# NE555DWTZD.net
KiCad netlist of a schematic drawn in Altium Designer
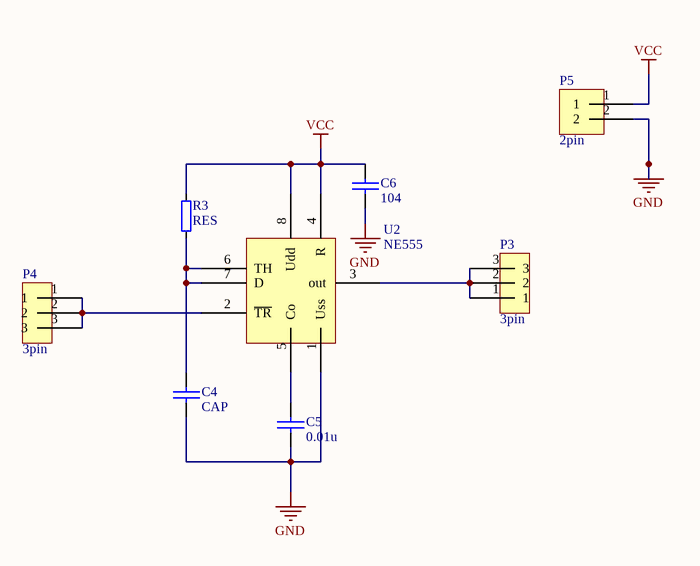
[diagram p0: NE555DWTZD.SchDoc]

(export (version "E")
  (design (tool "Eeschema 10.0.6"))
  (components
    (comp (ref "C4") (value "CAP") (footprint "RAD0.1") (libsource (lib "fish") (part "CAP")))
    (comp (ref "C5") (value "0.01u") (footprint "RAD0.1") (libsource (lib "fish") (part "CAP")))
    (comp (ref "C6") (value "104") (footprint "RAD0.1") (libsource (lib "fish") (part "CAP")))
    (comp (ref "P3") (value "3pin") (footprint "3PIN排针") (libsource (lib "") (part "3pin_1")))
    (comp (ref "P4") (value "3pin") (footprint "3PIN排针") (libsource (lib "fish") (part "3pin")))
    (comp (ref "P5") (value "2pin") (footprint "2pin针") (libsource (lib "fish") (part "2pin")))
    (comp (ref "R3") (value "RES") (footprint "AXIAL0.4") (libsource (lib "fish") (part "RES")))
    (comp (ref "U2") (value "NE555") (footprint "8pin座") (libsource (lib "fish") (part "NE555")))
  )
  (nets
    (net (code "1") (name "GND") (class "Default")
      (node (ref "C4") (pin "2") (pinfunction "2_2") (pintype "passive"))
      (node (ref "C5") (pin "2") (pinfunction "2_2") (pintype "passive"))
      (node (ref "C6") (pin "2") (pinfunction "2_2") (pintype "passive"))
      (node (ref "P5") (pin "2") (pinfunction "2_2") (pintype "passive"))
      (node (ref "U2") (pin "1") (pinfunction "Uss_1") (pintype "passive"))
    )
    (net (code "2") (name "Net-(U2-Co)") (class "Default")
      (node (ref "C5") (pin "1") (pinfunction "1_1") (pintype "passive"))
      (node (ref "U2") (pin "5") (pinfunction "Co_5") (pintype "passive"))
    )
    (net (code "3") (name "Net-(U2-D)") (class "Default")
      (node (ref "C4") (pin "1") (pinfunction "1_1") (pintype "passive"))
      (node (ref "R3") (pin "1") (pinfunction "1_1") (pintype "passive"))
      (node (ref "U2") (pin "6") (pinfunction "TH_6") (pintype "passive"))
      (node (ref "U2") (pin "7") (pinfunction "D_7") (pintype "passive"))
    )
    (net (code "4") (name "Net-(U2-out)") (class "Default")
      (node (ref "P3") (pin "1") (pinfunction "1_1") (pintype "passive"))
      (node (ref "P3") (pin "2") (pinfunction "2_2") (pintype "passive"))
      (node (ref "P3") (pin "3") (pinfunction "3_3") (pintype "passive"))
      (node (ref "U2") (pin "3") (pinfunction "out_3") (pintype "passive"))
    )
    (net (code "5") (name "Net-(U2-~{TR})") (class "Default")
      (node (ref "P4") (pin "1") (pinfunction "1_1") (pintype "passive"))
      (node (ref "P4") (pin "2") (pinfunction "2_2") (pintype "passive"))
      (node (ref "P4") (pin "3") (pinfunction "3_3") (pintype "passive"))
      (node (ref "U2") (pin "2") (pinfunction "~{TR}_2") (pintype "passive"))
    )
    (net (code "6") (name "VCC") (class "Default")
      (node (ref "C6") (pin "1") (pinfunction "1_1") (pintype "passive"))
      (node (ref "P5") (pin "1") (pinfunction "1_1") (pintype "passive"))
      (node (ref "R3") (pin "2") (pinfunction "2_2") (pintype "passive"))
      (node (ref "U2") (pin "4") (pinfunction "R_4") (pintype "passive"))
      (node (ref "U2") (pin "8") (pinfunction "Udd_8") (pintype "passive"))
    )
  )
)
